# Geass_Chaser_Nov_12_2025.net
KiCad netlist of a schematic drawn in EasyEDA
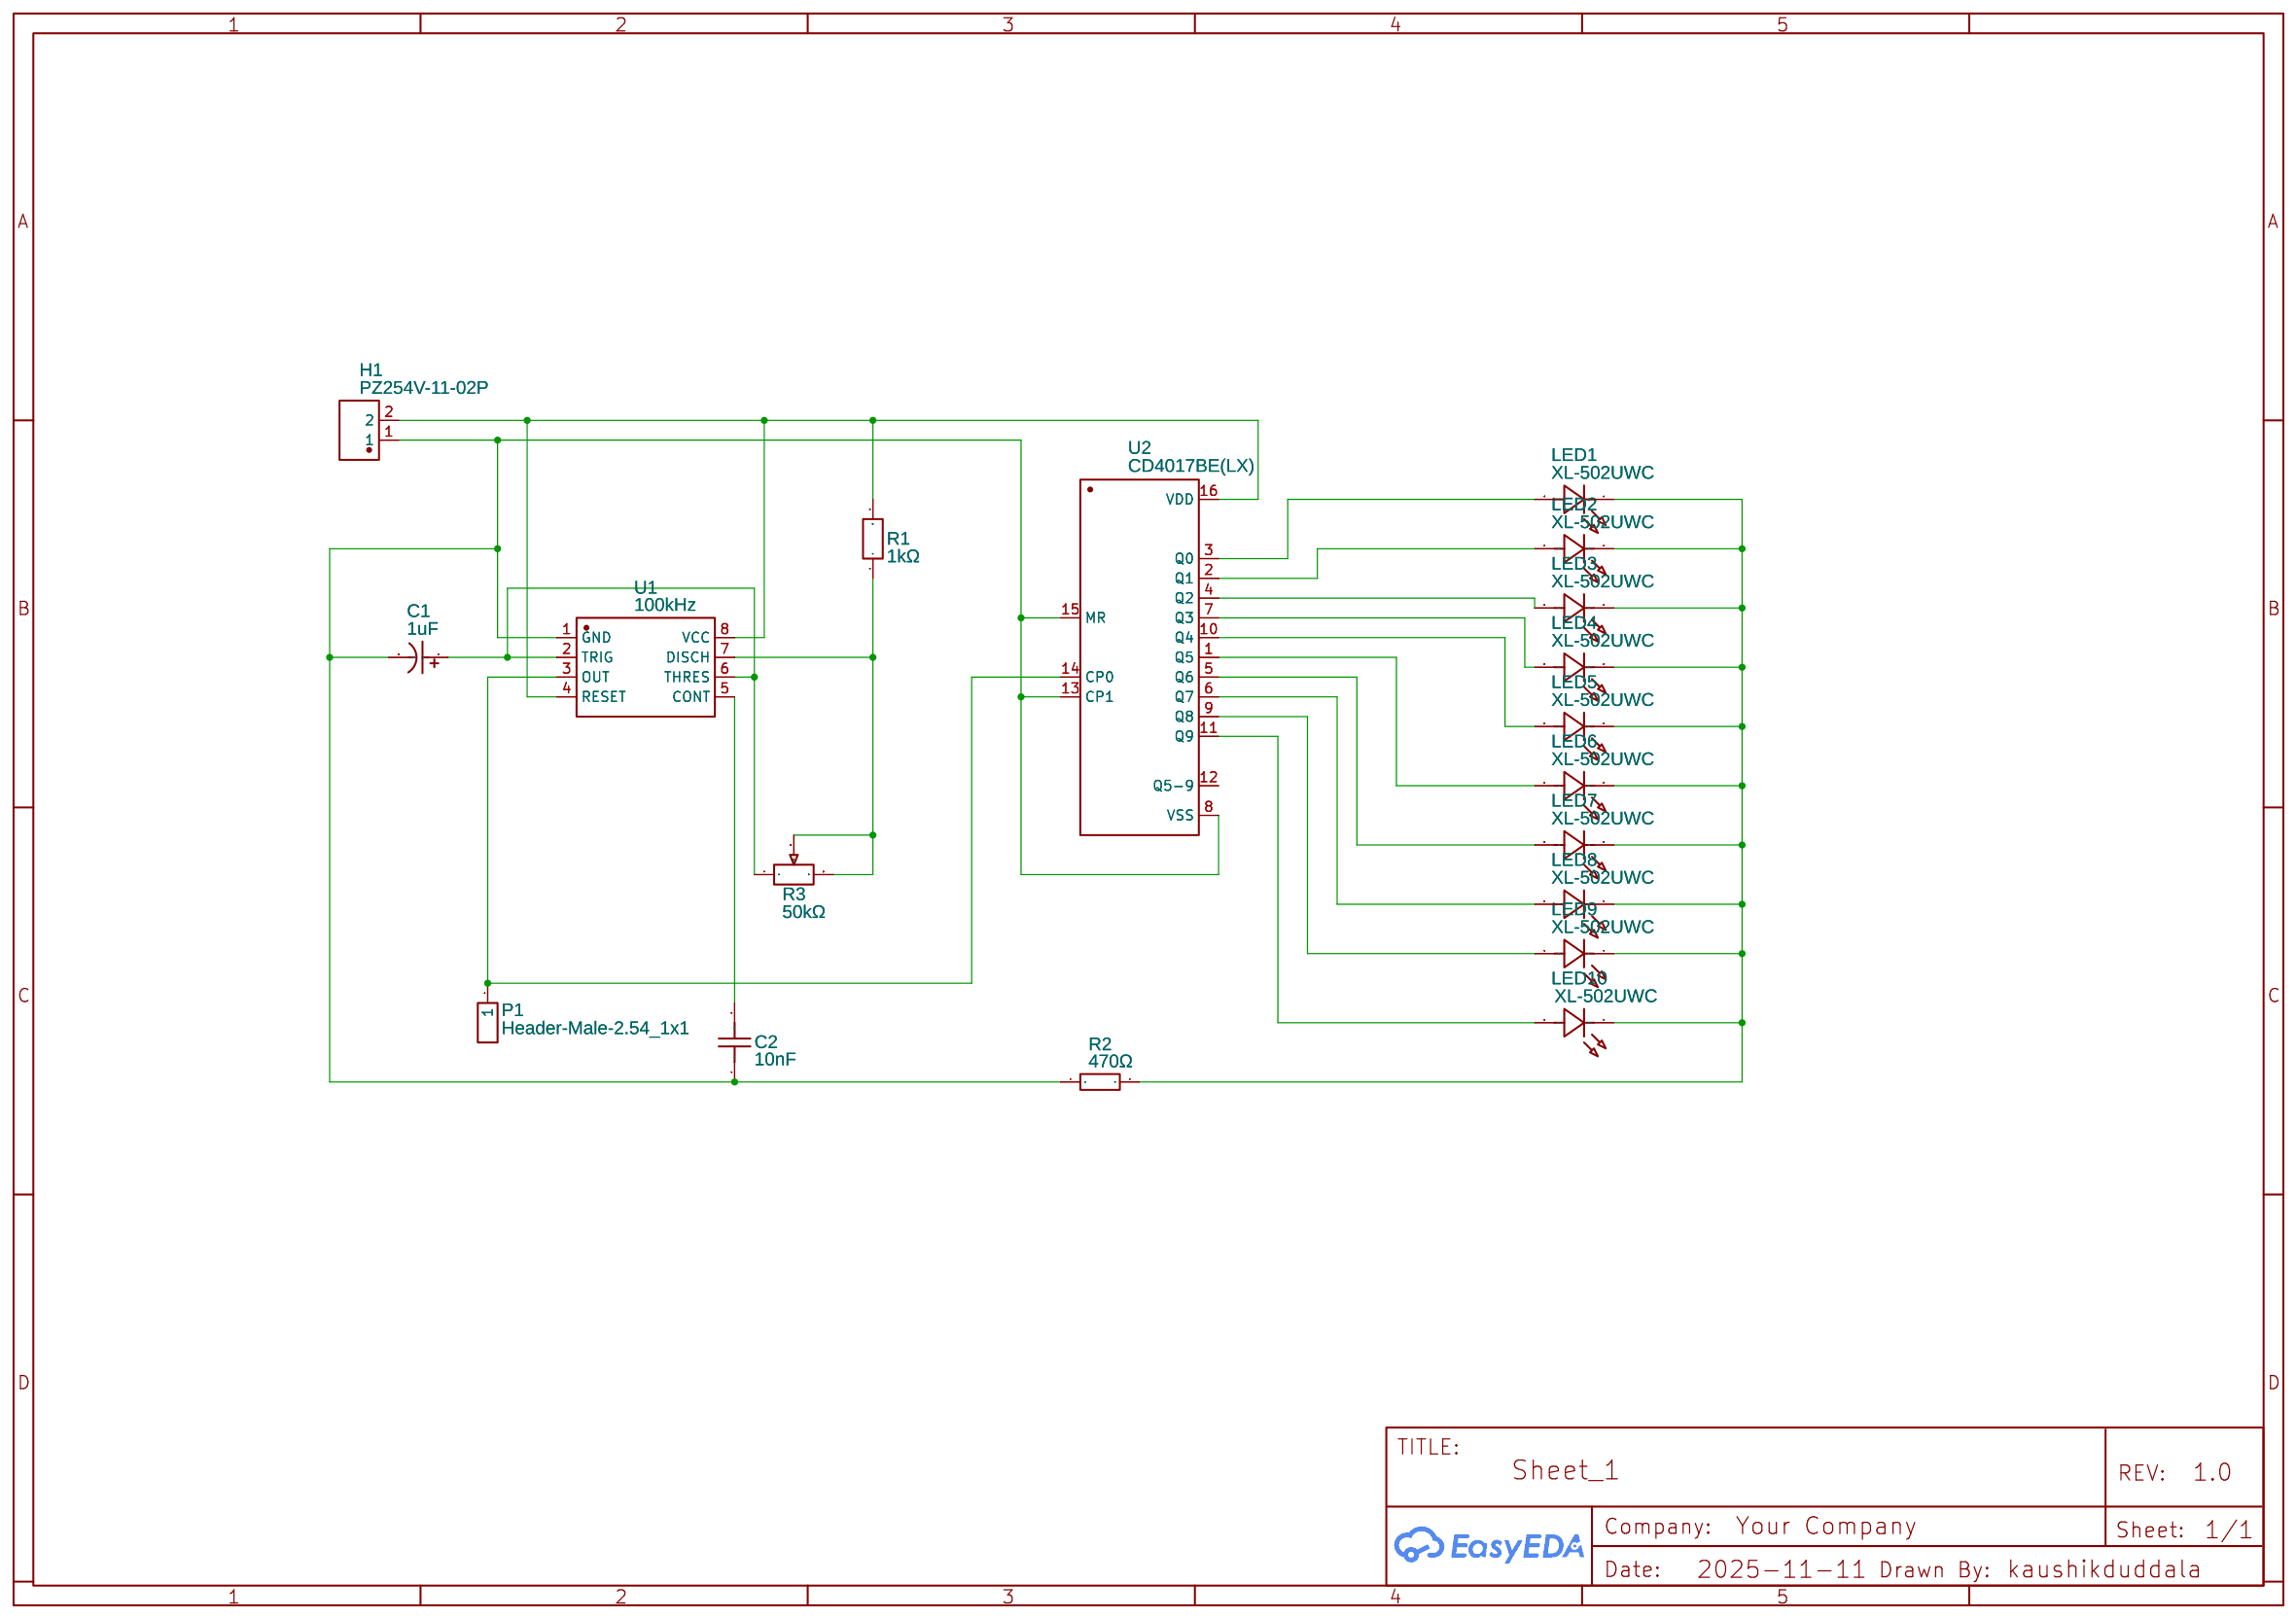
[diagram p0: schematic sheet]

(export (version "E")
  (design (tool "Eeschema 10.0.6"))
  (components
    (comp (ref "C1")
      (value "1uF")
      (fields (field (name "Manufacturer Part") "KF010M050C110A") (field (name "Manufacturer") "CapXon(丰宾)"))
      (libsource (lib "") (part "KF010M050C110A"))
    )
    (comp (ref "C2")
      (value "10nF")
      (fields (field (name "Manufacturer Part") "N09F1B103MN0B0S0N0") (field (name "Manufacturer") "STE(松田)"))
      (libsource (lib "") (part "N09F1B103MN0B0S0N0"))
    )
    (comp (ref "H1")
      (value "PZ254V-11-02P")
      (fields (field (name "Manufacturer") "XFCN(兴飞)"))
      (libsource (lib "") (part "PZ254V-11-02P"))
    )
    (comp (ref "LED1")
      (value "XL-502UWC")
      (fields (field (name "Manufacturer") "XINGLIGHT(成兴光)"))
      (libsource (lib "") (part "XL-502UWC"))
    )
    (comp (ref "LED2")
      (value "XL-502UWC")
      (fields (field (name "Manufacturer") "XINGLIGHT(成兴光)"))
      (libsource (lib "") (part "XL-502UWC"))
    )
    (comp (ref "LED3")
      (value "XL-502UWC")
      (fields (field (name "Manufacturer") "XINGLIGHT(成兴光)"))
      (libsource (lib "") (part "XL-502UWC"))
    )
    (comp (ref "LED4")
      (value "XL-502UWC")
      (fields (field (name "Manufacturer") "XINGLIGHT(成兴光)"))
      (libsource (lib "") (part "XL-502UWC"))
    )
    (comp (ref "LED5")
      (value "XL-502UWC")
      (fields (field (name "Manufacturer") "XINGLIGHT(成兴光)"))
      (libsource (lib "") (part "XL-502UWC"))
    )
    (comp (ref "LED6")
      (value "XL-502UWC")
      (fields (field (name "Manufacturer") "XINGLIGHT(成兴光)"))
      (libsource (lib "") (part "XL-502UWC"))
    )
    (comp (ref "LED7")
      (value "XL-502UWC")
      (fields (field (name "Manufacturer") "XINGLIGHT(成兴光)"))
      (libsource (lib "") (part "XL-502UWC"))
    )
    (comp (ref "LED8")
      (value "XL-502UWC")
      (fields (field (name "Manufacturer") "XINGLIGHT(成兴光)"))
      (libsource (lib "") (part "XL-502UWC"))
    )
    (comp (ref "LED9")
      (value "XL-502UWC")
      (fields (field (name "Manufacturer") "XINGLIGHT(成兴光)"))
      (libsource (lib "") (part "XL-502UWC"))
    )
    (comp (ref "LED10")
      (value "XL-502UWC")
      (fields (field (name "Manufacturer") "XINGLIGHT(成兴光)"))
      (libsource (lib "") (part "XL-502UWC"))
    )
    (comp (ref "P1")
      (value "Header-Male-2.54_1x1")
      (fields (field (name "Manufacturer Part") "2.54-1*1P针") (field (name "Manufacturer") "BOOMELE(博穆精密)"))
      (libsource (lib "") (part "Header-Male-2.54_1x1"))
    )
    (comp (ref "R1")
      (value "1kΩ")
      (fields (field (name "Manufacturer Part") "MF1/4W-1KΩ±1%T52") (field (name "Manufacturer") "华星机电"))
      (libsource (lib "") (part "MF1/4W-1KΩ±1%T52"))
    )
    (comp (ref "R2")
      (value "470Ω")
      (fields
        (field (name "Manufacturer Part") "MFR0W4F4700A50")
        (field (name "Manufacturer") "UNI-ROYAL(厚声)")
      )
      (libsource (lib "") (part "MFR0W4F4700A50"))
    )
    (comp (ref "R3")
      (value "50kΩ")
      (fields (field (name "Manufacturer Part") "3296X-1-503") (field (name "Manufacturer") "BOCHEN(博晨)"))
      (libsource (lib "") (part "3296X-1-503_C118912"))
    )
    (comp (ref "U1")
      (value "100kHz")
      (fields (field (name "Manufacturer Part") "NE555P") (field (name "Manufacturer") "TI(德州仪器)"))
      (libsource (lib "") (part "NE555P"))
    )
    (comp (ref "U2")
      (value "CD4017BE(LX)")
      (fields (field (name "Manufacturer") "LX(灵星芯微)"))
      (libsource (lib "") (part "CD4017BE(LX)"))
    )
  )
  (nets
    (net (code "1") (name "Net-(LED1-A)") (class "Default")
      (node (ref "LED1") (pin "2") (pinfunction "A_2") (pintype "unspecified"))
      (node (ref "U2") (pin "3") (pinfunction "Q0_3") (pintype "unspecified"))
    )
    (net (code "2") (name "Net-(LED1-K)") (class "Default")
      (node (ref "LED1") (pin "1") (pinfunction "K_1") (pintype "unspecified"))
      (node (ref "LED10") (pin "1") (pinfunction "K_1") (pintype "unspecified"))
      (node (ref "LED2") (pin "1") (pinfunction "K_1") (pintype "unspecified"))
      (node (ref "LED3") (pin "1") (pinfunction "K_1") (pintype "unspecified"))
      (node (ref "LED4") (pin "1") (pinfunction "K_1") (pintype "unspecified"))
      (node (ref "LED5") (pin "1") (pinfunction "K_1") (pintype "unspecified"))
      (node (ref "LED6") (pin "1") (pinfunction "K_1") (pintype "unspecified"))
      (node (ref "LED7") (pin "1") (pinfunction "K_1") (pintype "unspecified"))
      (node (ref "LED8") (pin "1") (pinfunction "K_1") (pintype "unspecified"))
      (node (ref "LED9") (pin "1") (pinfunction "K_1") (pintype "unspecified"))
      (node (ref "R2") (pin "2") (pinfunction "2_2") (pintype "input"))
    )
    (net (code "3") (name "Net-(LED2-A)") (class "Default")
      (node (ref "LED2") (pin "2") (pinfunction "A_2") (pintype "unspecified"))
      (node (ref "U2") (pin "2") (pinfunction "Q1_2") (pintype "unspecified"))
    )
    (net (code "4") (name "Net-(LED3-A)") (class "Default")
      (node (ref "LED3") (pin "2") (pinfunction "A_2") (pintype "unspecified"))
      (node (ref "U2") (pin "4") (pinfunction "Q2_4") (pintype "unspecified"))
    )
    (net (code "5") (name "Net-(LED4-A)") (class "Default")
      (node (ref "LED4") (pin "2") (pinfunction "A_2") (pintype "unspecified"))
      (node (ref "U2") (pin "7") (pinfunction "Q3_7") (pintype "unspecified"))
    )
    (net (code "6") (name "Net-(LED5-A)") (class "Default")
      (node (ref "LED5") (pin "2") (pinfunction "A_2") (pintype "unspecified"))
      (node (ref "U2") (pin "10") (pinfunction "Q4_10") (pintype "unspecified"))
    )
    (net (code "7") (name "Net-(LED6-A)") (class "Default")
      (node (ref "LED6") (pin "2") (pinfunction "A_2") (pintype "unspecified"))
      (node (ref "U2") (pin "1") (pinfunction "Q5_1") (pintype "unspecified"))
    )
    (net (code "8") (name "Net-(LED7-A)") (class "Default")
      (node (ref "LED7") (pin "2") (pinfunction "A_2") (pintype "unspecified"))
      (node (ref "U2") (pin "5") (pinfunction "Q6_5") (pintype "unspecified"))
    )
    (net (code "9") (name "Net-(LED8-A)") (class "Default")
      (node (ref "LED8") (pin "2") (pinfunction "A_2") (pintype "unspecified"))
      (node (ref "U2") (pin "6") (pinfunction "Q7_6") (pintype "unspecified"))
    )
    (net (code "10") (name "Net-(LED9-A)") (class "Default")
      (node (ref "LED9") (pin "2") (pinfunction "A_2") (pintype "unspecified"))
      (node (ref "U2") (pin "9") (pinfunction "Q8_9") (pintype "unspecified"))
    )
    (net (code "11") (name "Net-(LED10-A)") (class "Default")
      (node (ref "LED10") (pin "2") (pinfunction "A_2") (pintype "unspecified"))
      (node (ref "U2") (pin "11") (pinfunction "Q9_11") (pintype "unspecified"))
    )
    (net (code "12") (name "Net-(U1-CONT)") (class "Default")
      (node (ref "C2") (pin "2") (pinfunction "2_2") (pintype "unspecified"))
      (node (ref "U1") (pin "5") (pinfunction "CONT_5") (pintype "unspecified"))
    )
    (net (code "13") (name "Net-(U1-DISCH)") (class "Default")
      (node (ref "R1") (pin "1") (pinfunction "1_1") (pintype "unspecified"))
      (node (ref "R3") (pin "2") (pinfunction "2_2") (pintype "input"))
      (node (ref "R3") (pin "3") (pinfunction "3_3") (pintype "input"))
      (node (ref "U1") (pin "7") (pinfunction "DISCH_7") (pintype "unspecified"))
    )
    (net (code "14") (name "Net-(U1-GND)") (class "Default")
      (node (ref "C1") (pin "2") (pinfunction "2_2") (pintype "input"))
      (node (ref "C2") (pin "1") (pinfunction "1_1") (pintype "unspecified"))
      (node (ref "H1") (pin "1") (pinfunction "1_1") (pintype "unspecified"))
      (node (ref "R2") (pin "1") (pinfunction "1_1") (pintype "input"))
      (node (ref "U1") (pin "1") (pinfunction "GND_1") (pintype "unspecified"))
      (node (ref "U2") (pin "13") (pinfunction "CP1_13") (pintype "unspecified"))
      (node (ref "U2") (pin "15") (pinfunction "MR_15") (pintype "unspecified"))
      (node (ref "U2") (pin "8") (pinfunction "VSS_8") (pintype "unspecified"))
    )
    (net (code "15") (name "Net-(U1-OUT)") (class "Default")
      (node (ref "P1") (pin "1") (pinfunction "1_1") (pintype "input"))
      (node (ref "U1") (pin "3") (pinfunction "OUT_3") (pintype "unspecified"))
      (node (ref "U2") (pin "14") (pinfunction "CP0_14") (pintype "unspecified"))
    )
    (net (code "16") (name "Net-(U1-RESET)") (class "Default")
      (node (ref "H1") (pin "2") (pinfunction "2_2") (pintype "unspecified"))
      (node (ref "R1") (pin "2") (pinfunction "2_2") (pintype "unspecified"))
      (node (ref "U1") (pin "4") (pinfunction "RESET_4") (pintype "unspecified"))
      (node (ref "U1") (pin "8") (pinfunction "VCC_8") (pintype "unspecified"))
      (node (ref "U2") (pin "16") (pinfunction "VDD_16") (pintype "unspecified"))
    )
    (net (code "17") (name "Net-(U1-THRES)") (class "Default")
      (node (ref "C1") (pin "1") (pinfunction "1_1") (pintype "input"))
      (node (ref "R3") (pin "1") (pinfunction "1_1") (pintype "input"))
      (node (ref "U1") (pin "2") (pinfunction "TRIG_2") (pintype "unspecified"))
      (node (ref "U1") (pin "6") (pinfunction "THRES_6") (pintype "unspecified"))
    )
    (net (code "18") (name "unconnected-(U2-Q5-9-Pad12)") (class "Default")
      (node (ref "U2") (pin "12") (pinfunction "Q5-9_12") (pintype "unspecified"))
    )
  )
)
